# reset.net
KiCad netlist of a schematic drawn in Altium Designer
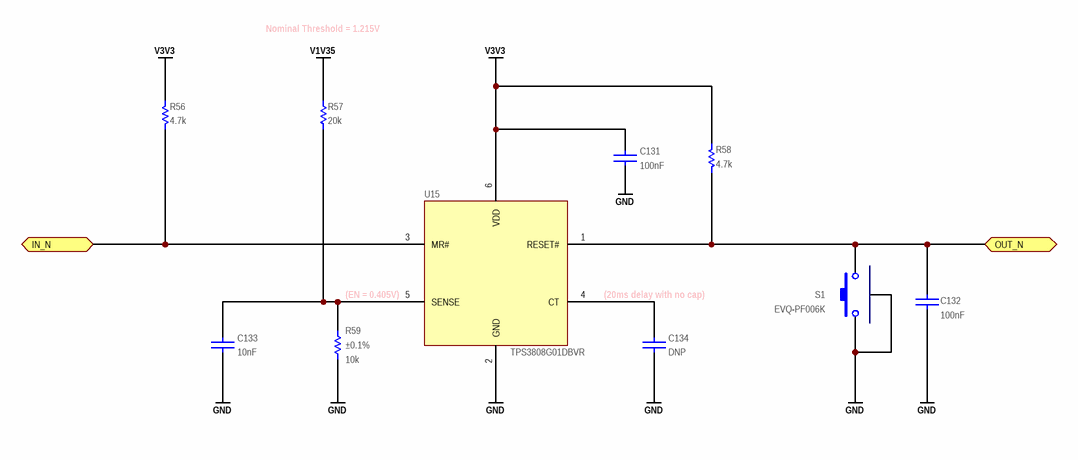
[diagram p0: reset.SchDoc]

(export (version "E")
  (design (tool "Eeschema 10.0.6"))
  (components
    (comp (ref "C131")
      (value "100nF")
      (footprint "CAPC100X50X55L25N")
      (description "Ceramic Capacitor 100nF ±10% 50V X7R 0402")
      (fields (field (name "MANUFACTURER") "Murata") (field (name "TOLERANCE") "±10%"))
      (libsource (lib "generic") (part "CAP"))
    )
    (comp (ref "C132")
      (value "100nF")
      (footprint "CAPC100X50X55L25N")
      (description "Ceramic Capacitor 100nF ±10% 50V X7R 0402")
      (fields (field (name "MANUFACTURER") "Murata") (field (name "TOLERANCE") "±10%"))
      (libsource (lib "") (part "CAP_1"))
    )
    (comp (ref "C133")
      (value "10nF")
      (footprint "CAPC100X50X55L25N")
      (description "Ceramic Capacitor 10nF ±10% 50V X7R 0402")
      (fields (field (name "MANUFACTURER") "Murata") (field (name "TOLERANCE") "±10%"))
      (libsource (lib "generic") (part "CAP"))
    )
    (comp (ref "C134")
      (value "CAP 0805")
      (footprint "CAPC200X125X145L45N")
      (description "Capacitor 0805")
      (fields (field (name "DO NOT PLACE") "DNP"))
      (libsource (lib "generic") (part "CAP"))
    )
    (comp (ref "R56")
      (value "4.7k")
      (footprint "RESC1005X40N")
      (description "Thick Film Resistor 4.7k ±1% 0.1W 75V 0402")
      (fields (field (name "TOLERANCE") "±1%") (field (name "MANUFACTURER") "Panasonic"))
      (libsource (lib "generic") (part "RES"))
    )
    (comp (ref "R57")
      (value "20k")
      (footprint "RESC2012X70N")
      (description "Thin Film Resistor 20k ±0.1% 0.125W 100V 0805")
      (fields (field (name "TOLERANCE") "±0.1%") (field (name "MANUFACTURER") "Panasonic"))
      (libsource (lib "generic") (part "RES"))
    )
    (comp (ref "R58")
      (value "4.7k")
      (footprint "RESC1005X40N")
      (description "Thick Film Resistor 4.7k ±1% 0.1W 75V 0402")
      (fields (field (name "TOLERANCE") "±1%") (field (name "MANUFACTURER") "Panasonic"))
      (libsource (lib "generic") (part "RES"))
    )
    (comp (ref "R59")
      (value "10k")
      (footprint "RESC2012X70N")
      (description "Thin Film Resistor 10k ±0.1% 0.125W 100V 0805")
      (fields
        (field (name "TOLERANCE") "±0.1%")
        (field (name "MANUFACTURER") "Panasonic")
        (field (name "VOLTAGE") "100")
      )
      (libsource (lib "generic") (part "RES"))
    )
    (comp (ref "S1")
      (value "EVQ-PF006K")
      (footprint "EVQ-PF006K")
      (description "Tactile Switch; Normally Open")
      (fields (field (name "MANUFACTURER") "Panasonic"))
      (libsource (lib "panasonic") (part "EVQ-PF006K"))
    )
    (comp (ref "U15")
      (value "TPS3808G01DBVR")
      (footprint "DBV-6")
      (description "Low Quiescent Current, Programmable-Delay  Supervisory Circuit")
      (fields (field (name "MANUFACTURER") "Texas Instruments"))
      (libsource (lib "shit") (part "TPS3808"))
    )
  )
  (nets
    (net (code "1") (name "/IN_N") (class "Default")
      (node (ref "R56") (pin "1") (pinfunction "1_1") (pintype "passive"))
      (node (ref "U15") (pin "3") (pinfunction "MR#_3") (pintype "passive"))
    )
    (net (code "2") (name "/OUT_N") (class "Default")
      (node (ref "C132") (pin "2") (pinfunction "2_2") (pintype "passive"))
      (node (ref "R58") (pin "1") (pinfunction "1_1") (pintype "passive"))
      (node (ref "S1") (pin "2") (pinfunction "2_2") (pintype "passive"))
      (node (ref "U15") (pin "1") (pinfunction "RESET#_1") (pintype "passive"))
    )
    (net (code "3") (name "GND") (class "Default")
      (node (ref "C131") (pin "2") (pinfunction "2_2") (pintype "passive"))
      (node (ref "C132") (pin "1") (pinfunction "1_1") (pintype "passive"))
      (node (ref "C133") (pin "2") (pinfunction "2_2") (pintype "passive"))
      (node (ref "C134") (pin "2") (pinfunction "2_2") (pintype "passive"))
      (node (ref "R59") (pin "1") (pinfunction "1_1") (pintype "passive"))
      (node (ref "S1") (pin "1") (pinfunction "1_1") (pintype "passive"))
      (node (ref "S1") (pin "3") (pinfunction "3_3") (pintype "passive"))
      (node (ref "U15") (pin "2") (pinfunction "GND_2") (pintype "passive"))
    )
    (net (code "4") (name "Net-(U15-CT)") (class "Default")
      (node (ref "C134") (pin "1") (pinfunction "1_1") (pintype "passive"))
      (node (ref "U15") (pin "4") (pinfunction "CT_4") (pintype "passive"))
    )
    (net (code "5") (name "Net-(U15-SENSE)") (class "Default")
      (node (ref "C133") (pin "1") (pinfunction "1_1") (pintype "passive"))
      (node (ref "R57") (pin "1") (pinfunction "1_1") (pintype "passive"))
      (node (ref "R59") (pin "2") (pinfunction "2_2") (pintype "passive"))
      (node (ref "U15") (pin "5") (pinfunction "SENSE_5") (pintype "passive"))
    )
    (net (code "6") (name "V1V35") (class "Default")
      (node (ref "R57") (pin "2") (pinfunction "2_2") (pintype "passive"))
    )
    (net (code "7") (name "V3V3") (class "Default")
      (node (ref "C131") (pin "1") (pinfunction "1_1") (pintype "passive"))
      (node (ref "R56") (pin "2") (pinfunction "2_2") (pintype "passive"))
      (node (ref "R58") (pin "2") (pinfunction "2_2") (pintype "passive"))
      (node (ref "U15") (pin "6") (pinfunction "VDD_6") (pintype "passive"))
    )
  )
)
